# BLUENRG-345_REV1_Sheet2.net
KiCad netlist of a schematic drawn in Altium Designer
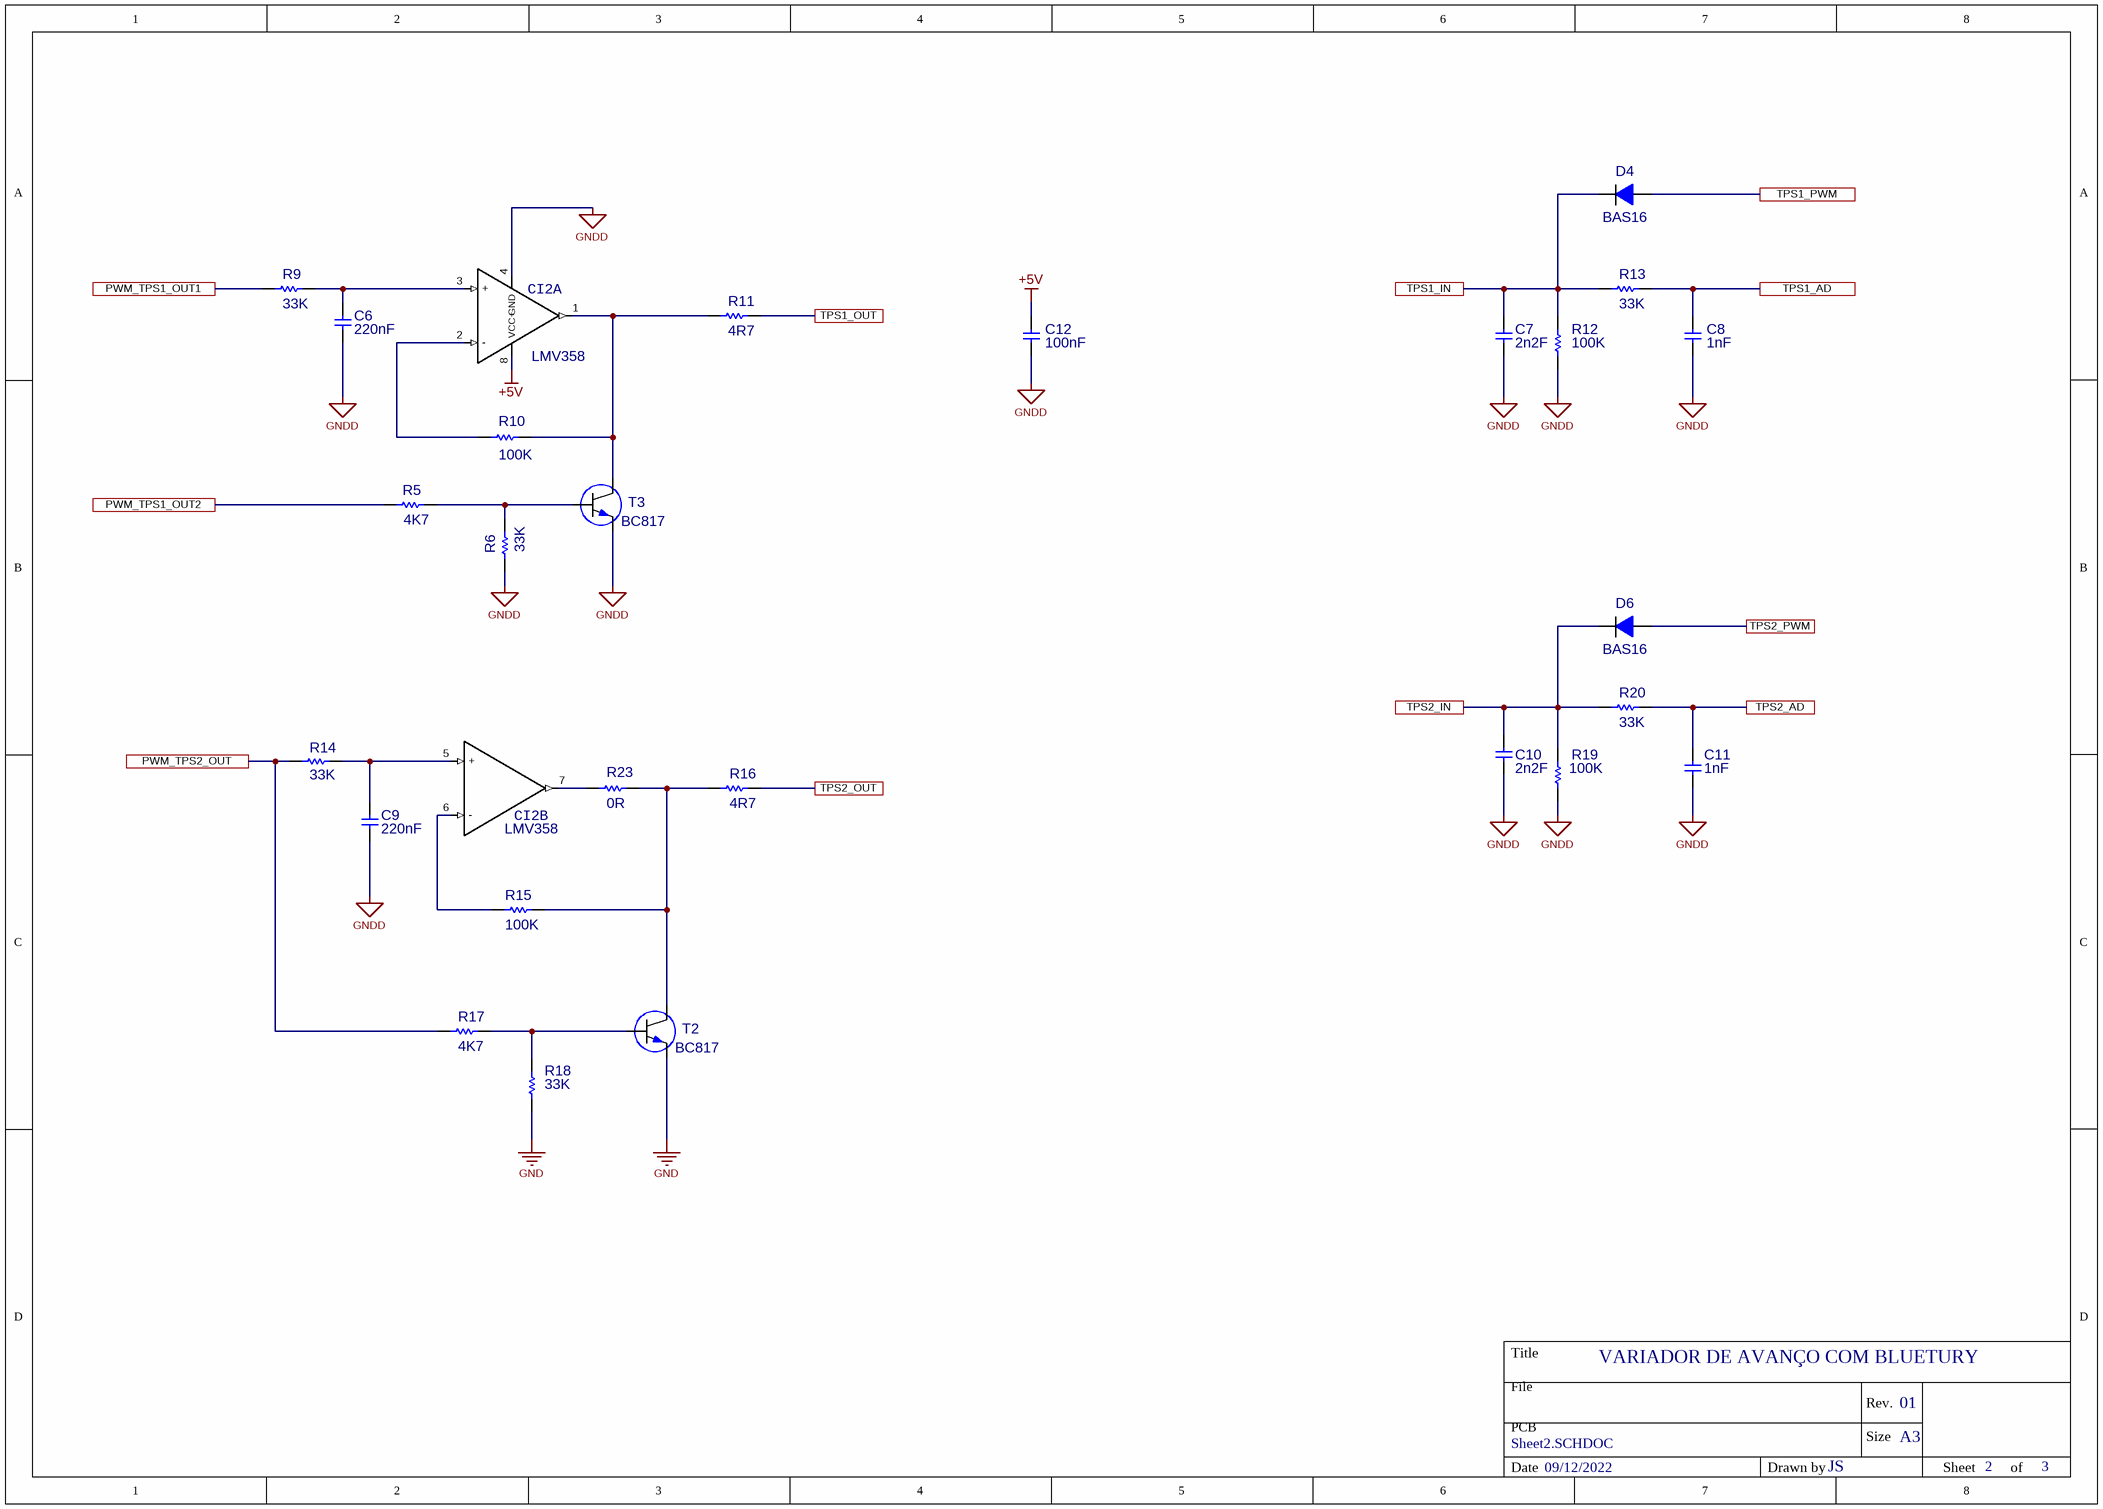
[diagram p0: BLUENRG-345_REV1_Sheet2.SchDoc]

(export (version "E")
  (design (tool "Eeschema 10.0.6"))
  (components
    (comp (ref "C6")
      (value "220nF")
      (footprint "C0402_REV1")
      (description "CAPACITOR 0402 220NF / 16V X7R 10%")
      (fields (field (name "Comment") "C0402"))
      (libsource (lib "SMD_Geral") (part "CAP_0402 220nF 10% 16V X7R"))
    )
    (comp (ref "C7")
      (value "2n2F")
      (footprint "C0402_REV1")
      (description "CAPACITOR 0402 2n2F / 50V C0G 5%")
      (fields (field (name "Comment") "C0402"))
      (libsource (lib "SMD_Geral") (part "CAP_0402 2n2F 5% 50V X7R"))
    )
    (comp (ref "C8")
      (value "1nF")
      (footprint "C0402_REV1")
      (description "CAPACITOR 0402 1NF / 50V C0G 5%")
      (fields (field (name "Comment") "C0402"))
      (libsource (lib "SMD_Geral") (part "CAP_0402 1nF 5% 50V X7R"))
    )
    (comp (ref "C9")
      (value "220nF")
      (footprint "C0402_REV1")
      (description "CAPACITOR 0402 220NF / 16V X7R 10%")
      (fields (field (name "Comment") "C0402"))
      (libsource (lib "SMD_Geral") (part "CAP_0402 220nF 10% 16V X7R"))
    )
    (comp (ref "C10")
      (value "2n2F")
      (footprint "C0402_REV1")
      (description "CAPACITOR 0402 2n2F / 50V C0G 5%")
      (fields (field (name "Comment") "C0402"))
      (libsource (lib "SMD_Geral") (part "CAP_0402 2n2F 5% 50V X7R"))
    )
    (comp (ref "C11")
      (value "1nF")
      (footprint "C0402_REV1")
      (description "CAPACITOR 0402 1NF / 50V C0G 5%")
      (fields (field (name "Comment") "C0402"))
      (libsource (lib "SMD_Geral") (part "CAP_0402 1nF 5% 50V X7R"))
    )
    (comp (ref "C12")
      (value "100nF")
      (footprint "C0402_REV1")
      (description "CAPACITOR 0402 100NF / 50V X7R 10%")
      (fields (field (name "Comment") "C0402"))
      (libsource (lib "SMD_Geral") (part "CAP_0402 100nF 10% 50V X7R"))
    )
    (comp (ref "CI2")
      (value "LMV358")
      (footprint "TSSOP-8_REV1 - MINISO8")
      (description "CI AMPLIFICADOR OPERACIONAL LMV358IPT TSSOP8")
      (fields (field (name "Comment") "CI_LMV358_TSSOP8"))
      (libsource (lib "SMD_Geral") (part "CI_LMV358_TSSOP8"))
    )
    (comp (ref "D4")
      (value "BAS16")
      (footprint "SOD323_IPC")
      (description "DIODO DE SINAL BAS16 SOD323")
      (fields (field (name "Comment") "D_BAS16_SOD323"))
      (libsource (lib "SMD_Geral") (part "D_BAS16_SOD323"))
    )
    (comp (ref "D6")
      (value "BAS16")
      (footprint "SOD323_IPC")
      (description "DIODO DE SINAL BAS16 SOD323")
      (fields (field (name "Comment") "D_BAS16_SOD323"))
      (libsource (lib "SMD_Geral") (part "D_BAS16_SOD323"))
    )
    (comp (ref "R5")
      (value "4K7")
      (footprint "R0402_REV1")
      (description "RESISTOR 0402 4K7 1/16W 5%")
      (fields (field (name "Comment") "RES 0402 4K7 1/16W 5%"))
      (libsource (lib "SMD_Geral") (part "RES 0402 4K7 1/16W 5%"))
    )
    (comp (ref "R6")
      (value "33K")
      (footprint "R0402_REV1")
      (description "RESISTOR 0402 33K 1/16W 5%")
      (fields (field (name "Comment") "R0603"))
      (libsource (lib "SMD_Geral") (part "RES 0402 33K 1/16W 5%"))
    )
    (comp (ref "R9")
      (value "33K")
      (footprint "R0402_REV1")
      (description "RESISTOR 0402 33K 1/16W 5%")
      (fields (field (name "Comment") "R0603"))
      (libsource (lib "SMD_Geral") (part "RES 0402 33K 1/16W 5%"))
    )
    (comp (ref "R10")
      (value "100K")
      (footprint "R0402_REV1")
      (description "RESISTOR 0402 100K 1/16W 5%")
      (fields (field (name "Comment") "R0402"))
      (libsource (lib "SMD_Geral") (part "RES 0402 100K 1/16W 5%"))
    )
    (comp (ref "R11")
      (value "4R7")
      (footprint "R0402_REV1")
      (description "RESISTOR 0402 4R7 1/16W 5%")
      (fields (field (name "Comment") "RES 0402 4R7 1/16W 5%"))
      (libsource (lib "SMD_Geral") (part "RES 0402 4R7 1/16W 5%"))
    )
    (comp (ref "R12")
      (value "100K")
      (footprint "R0402_REV1")
      (description "RESISTOR 0402 100K 1/16W 5%")
      (fields (field (name "Comment") "R0402"))
      (libsource (lib "SMD_Geral") (part "RES 0402 100K 1/16W 5%"))
    )
    (comp (ref "R13")
      (value "33K")
      (footprint "R0402_REV1")
      (description "RESISTOR 0402 33K 1/16W 5%")
      (fields (field (name "Comment") "R0603"))
      (libsource (lib "SMD_Geral") (part "RES 0402 33K 1/16W 5%"))
    )
    (comp (ref "R14")
      (value "33K")
      (footprint "R0402_REV1")
      (description "RESISTOR 0402 33K 1/16W 5%")
      (fields (field (name "Comment") "R0603"))
      (libsource (lib "SMD_Geral") (part "RES 0402 33K 1/16W 5%"))
    )
    (comp (ref "R15")
      (value "100K")
      (footprint "R0402_REV1")
      (description "RESISTOR 0402 100K 1/16W 5%")
      (fields (field (name "Comment") "R0402"))
      (libsource (lib "SMD_Geral") (part "RES 0402 100K 1/16W 5%"))
    )
    (comp (ref "R16")
      (value "4R7")
      (footprint "R0402_REV1")
      (description "RESISTOR 0402 4R7 1/16W 5%")
      (fields (field (name "Comment") "RES 0402 4R7 1/16W 5%"))
      (libsource (lib "SMD_Geral") (part "RES 0402 4R7 1/16W 5%"))
    )
    (comp (ref "R17")
      (value "4K7")
      (footprint "R0402_REV1")
      (description "RESISTOR 0402 4K7 1/16W 5%")
      (fields (field (name "Comment") "RES 0402 4K7 1/16W 5%"))
      (libsource (lib "SMD_Geral") (part "RES 0402 4K7 1/16W 5%"))
    )
    (comp (ref "R18")
      (value "33K")
      (footprint "R0402_REV1")
      (description "RESISTOR 0402 33K 1/16W 5%")
      (fields (field (name "Comment") "R0603"))
      (libsource (lib "SMD_Geral") (part "RES 0402 33K 1/16W 5%"))
    )
    (comp (ref "R19")
      (value "100K")
      (footprint "R0402_REV1")
      (description "RESISTOR 0402 100K 1/16W 5%")
      (fields (field (name "Comment") "R0402"))
      (libsource (lib "SMD_Geral") (part "RES 0402 100K 1/16W 5%"))
    )
    (comp (ref "R20")
      (value "33K")
      (footprint "R0402_REV1")
      (description "RESISTOR 0402 33K 1/16W 5%")
      (fields (field (name "Comment") "R0603"))
      (libsource (lib "SMD_Geral") (part "RES 0402 33K 1/16W 5%"))
    )
    (comp (ref "R23")
      (value "0R")
      (footprint "R0402_REV1")
      (description "RESISTOR 0402 0R 1/16W 5%")
      (fields (field (name "Comment") "RES 0402 0R 1/16W 5%"))
      (libsource (lib "SMD_Geral") (part "RES 0402 0R 1/16W 5%"))
    )
    (comp (ref "T2")
      (value "BC817")
      (footprint "SOT23_REV1")
      (description "TRANSISTOR BIPOLAR DE SINAL BC817/40  SOT23")
      (libsource (lib "SMD_Geral") (part "T_BC817_SOT23"))
    )
    (comp (ref "T3")
      (value "BC817")
      (footprint "SOT23_REV1")
      (description "TRANSISTOR BIPOLAR DE SINAL BC817/40  SOT23")
      (libsource (lib "SMD_Geral") (part "T_BC817_SOT23"))
    )
  )
  (nets
    (net (code "1") (name "+5V") (class "Default")
      (node (ref "C12") (pin "2") (pinfunction "-_2") (pintype "passive"))
      (node (ref "CI2") (pin "8") (pinfunction "VCC+_8") (pintype "power_in"))
    )
    (net (code "2") (name "/PWM_TPS1_OUT1") (class "Default")
      (node (ref "R9") (pin "1") (pinfunction "1_1") (pintype "passive"))
    )
    (net (code "3") (name "/PWM_TPS1_OUT2") (class "Default")
      (node (ref "R5") (pin "1") (pinfunction "1_1") (pintype "passive"))
    )
    (net (code "4") (name "/PWM_TPS2_OUT") (class "Default")
      (node (ref "R14") (pin "1") (pinfunction "1_1") (pintype "passive"))
      (node (ref "R17") (pin "1") (pinfunction "1_1") (pintype "passive"))
    )
    (net (code "5") (name "/TPS1_AD") (class "Default")
      (node (ref "C8") (pin "1") (pinfunction "1_1") (pintype "passive"))
      (node (ref "R13") (pin "2") (pinfunction "2_2") (pintype "passive"))
    )
    (net (code "6") (name "/TPS1_IN") (class "Default")
      (node (ref "C7") (pin "1") (pinfunction "1_1") (pintype "passive"))
      (node (ref "D4") (pin "2") (pinfunction "K_2") (pintype "passive"))
      (node (ref "R12") (pin "2") (pinfunction "2_2") (pintype "passive"))
      (node (ref "R13") (pin "1") (pinfunction "1_1") (pintype "passive"))
    )
    (net (code "7") (name "/TPS1_OUT") (class "Default")
      (node (ref "R11") (pin "2") (pinfunction "2_2") (pintype "passive"))
    )
    (net (code "8") (name "/TPS1_PWM") (class "Default")
      (node (ref "D4") (pin "1") (pinfunction "A_1") (pintype "passive"))
    )
    (net (code "9") (name "/TPS2_AD") (class "Default")
      (node (ref "C11") (pin "1") (pinfunction "1_1") (pintype "passive"))
      (node (ref "R20") (pin "2") (pinfunction "2_2") (pintype "passive"))
    )
    (net (code "10") (name "/TPS2_IN") (class "Default")
      (node (ref "C10") (pin "1") (pinfunction "1_1") (pintype "passive"))
      (node (ref "D6") (pin "2") (pinfunction "K_2") (pintype "passive"))
      (node (ref "R19") (pin "2") (pinfunction "2_2") (pintype "passive"))
      (node (ref "R20") (pin "1") (pinfunction "1_1") (pintype "passive"))
    )
    (net (code "11") (name "/TPS2_OUT") (class "Default")
      (node (ref "R16") (pin "2") (pinfunction "2_2") (pintype "passive"))
    )
    (net (code "12") (name "/TPS2_PWM") (class "Default")
      (node (ref "D6") (pin "1") (pinfunction "A_1") (pintype "passive"))
    )
    (net (code "13") (name "GND") (class "Default")
      (node (ref "R18") (pin "1") (pinfunction "1_1") (pintype "passive"))
      (node (ref "T2") (pin "2") (pinfunction "E_2") (pintype "passive"))
    )
    (net (code "14") (name "GNDD") (class "Default")
      (node (ref "C10") (pin "2") (pinfunction "2_2") (pintype "passive"))
      (node (ref "C11") (pin "2") (pinfunction "2_2") (pintype "passive"))
      (node (ref "C12") (pin "1") (pinfunction "+_1") (pintype "passive"))
      (node (ref "C6") (pin "1") (pinfunction "1_1") (pintype "passive"))
      (node (ref "C7") (pin "2") (pinfunction "2_2") (pintype "passive"))
      (node (ref "C8") (pin "2") (pinfunction "2_2") (pintype "passive"))
      (node (ref "C9") (pin "1") (pinfunction "1_1") (pintype "passive"))
      (node (ref "CI2") (pin "4") (pinfunction "GND_4") (pintype "power_in"))
      (node (ref "R12") (pin "1") (pinfunction "1_1") (pintype "passive"))
      (node (ref "R19") (pin "1") (pinfunction "1_1") (pintype "passive"))
      (node (ref "R6") (pin "1") (pinfunction "1_1") (pintype "passive"))
      (node (ref "T3") (pin "2") (pinfunction "E_2") (pintype "passive"))
    )
    (net (code "15") (name "Net-(CI2A-+)") (class "Default")
      (node (ref "C6") (pin "2") (pinfunction "2_2") (pintype "passive"))
      (node (ref "CI2") (pin "3") (pinfunction "+_3") (pintype "input"))
      (node (ref "R9") (pin "2") (pinfunction "2_2") (pintype "passive"))
    )
    (net (code "16") (name "Net-(CI2A--)") (class "Default")
      (node (ref "CI2") (pin "2") (pinfunction "-_2") (pintype "input"))
      (node (ref "R10") (pin "1") (pinfunction "1_1") (pintype "passive"))
    )
    (net (code "17") (name "Net-(CI2A-OUT)") (class "Default")
      (node (ref "CI2") (pin "1") (pinfunction "OUT_1") (pintype "output"))
      (node (ref "R10") (pin "2") (pinfunction "2_2") (pintype "passive"))
      (node (ref "R11") (pin "1") (pinfunction "1_1") (pintype "passive"))
      (node (ref "T3") (pin "3") (pinfunction "C_3") (pintype "passive"))
    )
    (net (code "18") (name "Net-(CI2B-+)") (class "Default")
      (node (ref "C9") (pin "2") (pinfunction "2_2") (pintype "passive"))
      (node (ref "CI2") (pin "5") (pinfunction "+_5") (pintype "input"))
      (node (ref "R14") (pin "2") (pinfunction "2_2") (pintype "passive"))
    )
    (net (code "19") (name "Net-(CI2B--)") (class "Default")
      (node (ref "CI2") (pin "6") (pinfunction "-_6") (pintype "input"))
      (node (ref "R15") (pin "1") (pinfunction "1_1") (pintype "passive"))
    )
    (net (code "20") (name "Net-(CI2B-OUT)") (class "Default")
      (node (ref "CI2") (pin "7") (pinfunction "OUT_7") (pintype "output"))
      (node (ref "R23") (pin "1") (pinfunction "1_1") (pintype "passive"))
    )
    (net (code "21") (name "Net-(T2-B)") (class "Default")
      (node (ref "R17") (pin "2") (pinfunction "2_2") (pintype "passive"))
      (node (ref "R18") (pin "2") (pinfunction "2_2") (pintype "passive"))
      (node (ref "T2") (pin "1") (pinfunction "B_1") (pintype "passive"))
    )
    (net (code "22") (name "Net-(T2-C)") (class "Default")
      (node (ref "R15") (pin "2") (pinfunction "2_2") (pintype "passive"))
      (node (ref "R16") (pin "1") (pinfunction "1_1") (pintype "passive"))
      (node (ref "R23") (pin "2") (pinfunction "2_2") (pintype "passive"))
      (node (ref "T2") (pin "3") (pinfunction "C_3") (pintype "passive"))
    )
    (net (code "23") (name "Net-(T3-B)") (class "Default")
      (node (ref "R5") (pin "2") (pinfunction "2_2") (pintype "passive"))
      (node (ref "R6") (pin "2") (pinfunction "2_2") (pintype "passive"))
      (node (ref "T3") (pin "1") (pinfunction "B_1") (pintype "passive"))
    )
  )
)
